# Voltage_Controlled_Amplifier_v1.net
KiCad netlist of a schematic drawn in EAGLE
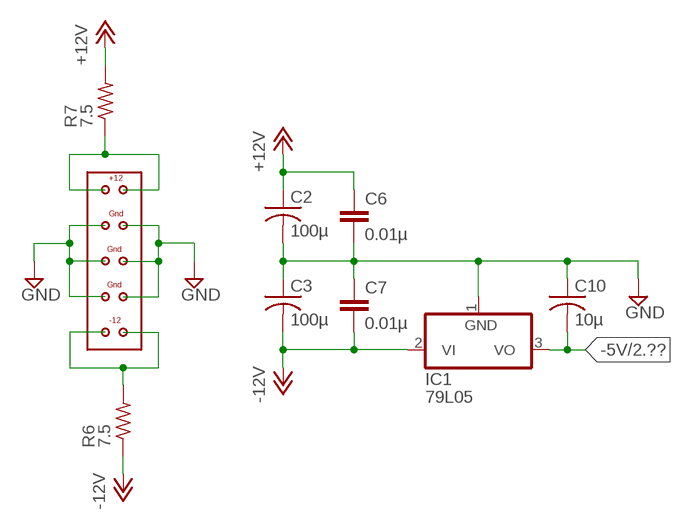
[diagram p0: schematic, sheet 1]
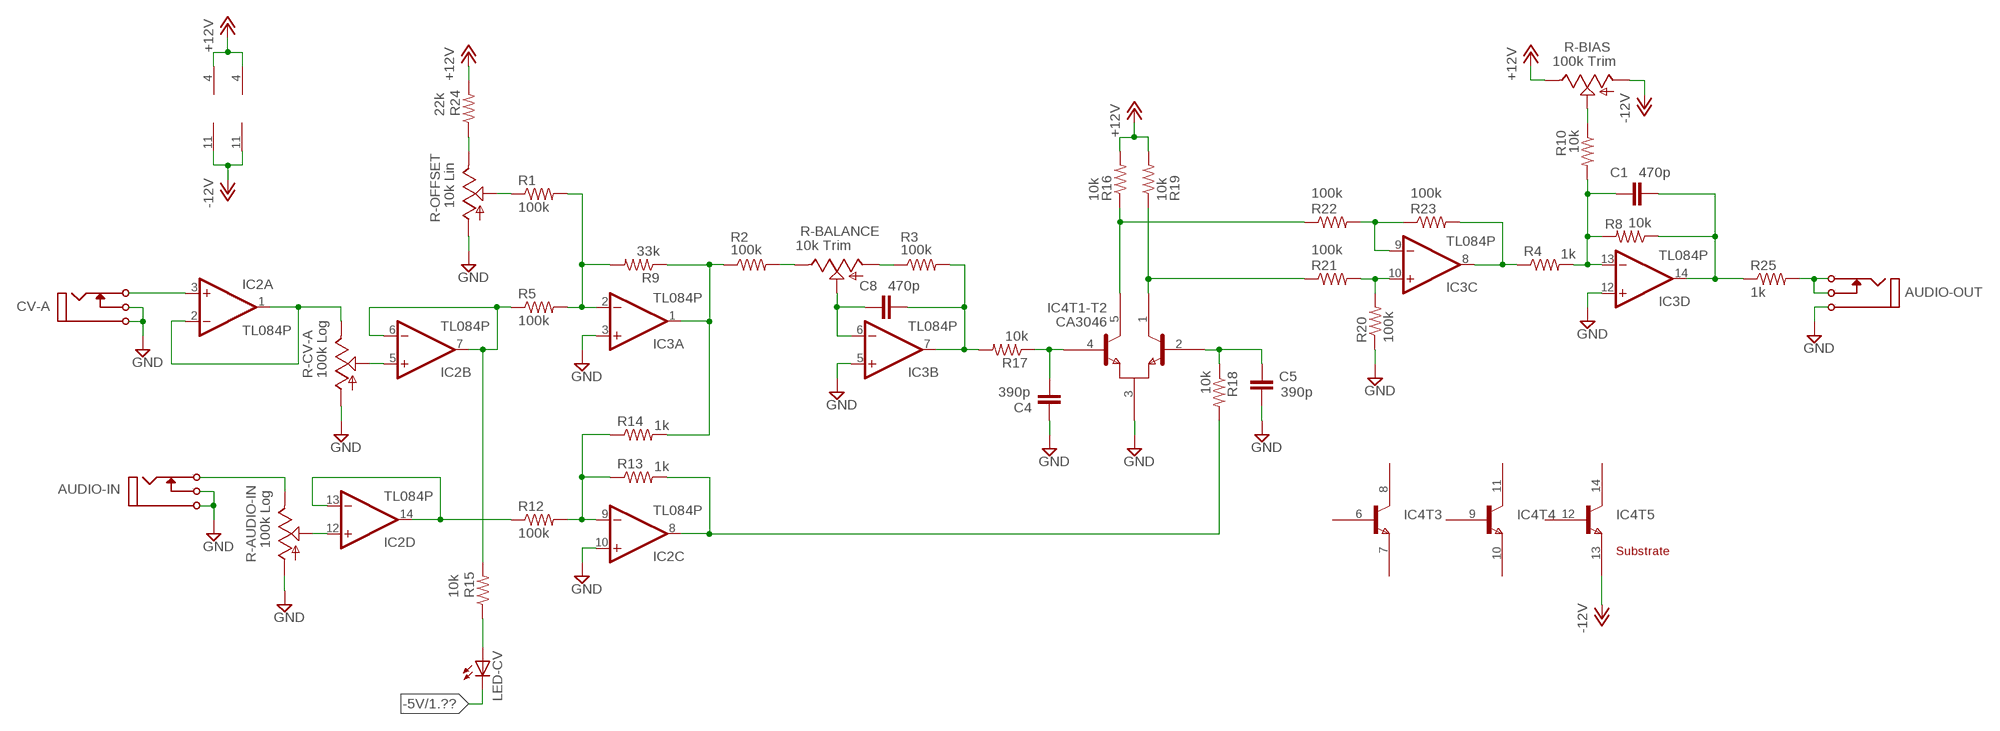
[diagram p1: schematic, sheet 2]

(export (version "E")
  (design (tool "Eeschema 10.0.6"))
  (components
    (comp (ref "AUDIO-IN")
      (value "I/O")
      (footprint "eagle-import:MONO_JACK")
      (libsource (lib "eagle-import") (part "MONO_JACK"))
    )
    (comp (ref "AUDIO-OUT")
      (value "I/O")
      (footprint "eagle-import:MONO_JACK")
      (libsource (lib "eagle-import") (part "MONO_JACK"))
    )
    (comp (ref "C1")
      (value "470p")
      (footprint "eagle-import:C2.5-2")
      (libsource (lib "eagle-import") (part "C2.5/2"))
    )
    (comp (ref "C4")
      (value "390p")
      (footprint "eagle-import:C2.5-2")
      (libsource (lib "eagle-import") (part "C2.5/2"))
    )
    (comp (ref "C5")
      (value "390p")
      (footprint "eagle-import:C2.5-2")
      (libsource (lib "eagle-import") (part "C2.5/2"))
    )
    (comp (ref "C8")
      (value "470p")
      (footprint "eagle-import:C2.5-2")
      (libsource (lib "eagle-import") (part "C2.5/2"))
    )
    (comp (ref "CV-A")
      (value "I/O")
      (footprint "eagle-import:MONO_JACK")
      (libsource (lib "eagle-import") (part "MONO_JACK"))
    )
    (comp (ref "IC2")
      (value "TL084P")
      (footprint "eagle-import:DIL14")
      (libsource (lib "eagle-import") (part "TL084P"))
    )
    (comp (ref "IC3")
      (value "TL084P")
      (footprint "eagle-import:DIL14")
      (libsource (lib "eagle-import") (part "TL084P"))
    )
    (comp (ref "IC4")
      (value "CA3046")
      (footprint "eagle-import:DIL14")
      (libsource (lib "eagle-import") (part "CA3046"))
    )
    (comp (ref "LED-CV")
      (value "TLLG4400")
      (footprint "eagle-import:LED3MM")
      (fields (field (name "MF") "VISHAY SEMICONDUCTOR"))
      (libsource (lib "eagle-import") (part "TLLG4400"))
    )
    (comp (ref "R-AUDIO-IN")
      (value "100k Log")
      (footprint "eagle-import:B64Y")
      (libsource (lib "eagle-import") (part "TRIM_US-B64Y"))
    )
    (comp (ref "R-BALANCE")
      (value "10k Trim")
      (footprint "eagle-import:B64Y")
      (libsource (lib "eagle-import") (part "TRIM_US-B64Y"))
    )
    (comp (ref "R-BIAS")
      (value "100k Trim")
      (footprint "eagle-import:B64Y")
      (libsource (lib "eagle-import") (part "TRIM_US-B64Y"))
    )
    (comp (ref "R-CV-A")
      (value "100k Log")
      (footprint "eagle-import:B64Y")
      (libsource (lib "eagle-import") (part "TRIM_US-B64Y"))
    )
    (comp (ref "R-OFFSET")
      (value "10k Lin")
      (footprint "eagle-import:B64Y")
      (libsource (lib "eagle-import") (part "TRIM_US-B64Y"))
    )
    (comp (ref "R1")
      (value "100k")
      (footprint "eagle-import:0204V")
      (libsource (lib "eagle-import") (part "R-US_0204/2V"))
    )
    (comp (ref "R2")
      (value "100k")
      (footprint "eagle-import:0204V")
      (libsource (lib "eagle-import") (part "R-US_0204/2V"))
    )
    (comp (ref "R3")
      (value "100k")
      (footprint "eagle-import:0204V")
      (libsource (lib "eagle-import") (part "R-US_0204/2V"))
    )
    (comp (ref "R4")
      (value "1k")
      (footprint "eagle-import:0204V")
      (libsource (lib "eagle-import") (part "R-US_0204/2V"))
    )
    (comp (ref "R5")
      (value "100k")
      (footprint "eagle-import:0204V")
      (libsource (lib "eagle-import") (part "R-US_0204/2V"))
    )
    (comp (ref "R8")
      (value "10k")
      (footprint "eagle-import:0204V")
      (libsource (lib "eagle-import") (part "R-US_0204/2V"))
    )
    (comp (ref "R9")
      (value "33k")
      (footprint "eagle-import:0204V")
      (libsource (lib "eagle-import") (part "R-US_0204/2V"))
    )
    (comp (ref "R10")
      (value "10k")
      (footprint "eagle-import:0204V")
      (libsource (lib "eagle-import") (part "R-US_0204/2V"))
    )
    (comp (ref "R12")
      (value "100k")
      (footprint "eagle-import:0204V")
      (libsource (lib "eagle-import") (part "R-US_0204/2V"))
    )
    (comp (ref "R13")
      (value "1k")
      (footprint "eagle-import:0204V")
      (libsource (lib "eagle-import") (part "R-US_0204/2V"))
    )
    (comp (ref "R14")
      (value "1k")
      (footprint "eagle-import:0204V")
      (libsource (lib "eagle-import") (part "R-US_0204/2V"))
    )
    (comp (ref "R15")
      (value "10k")
      (footprint "eagle-import:0204V")
      (libsource (lib "eagle-import") (part "R-US_0204/2V"))
    )
    (comp (ref "R16")
      (value "10k")
      (footprint "eagle-import:0204V")
      (libsource (lib "eagle-import") (part "R-US_0204/2V"))
    )
    (comp (ref "R17")
      (value "10k")
      (footprint "eagle-import:0204V")
      (libsource (lib "eagle-import") (part "R-US_0204/2V"))
    )
    (comp (ref "R18")
      (value "10k")
      (footprint "eagle-import:0204_7")
      (libsource (lib "eagle-import") (part "R-US_0204/7"))
    )
    (comp (ref "R19")
      (value "10k")
      (footprint "eagle-import:0204V")
      (libsource (lib "eagle-import") (part "R-US_0204/2V"))
    )
    (comp (ref "R20")
      (value "100k")
      (footprint "eagle-import:0204V")
      (libsource (lib "eagle-import") (part "R-US_0204/2V"))
    )
    (comp (ref "R21")
      (value "100k")
      (footprint "eagle-import:0204V")
      (libsource (lib "eagle-import") (part "R-US_0204/2V"))
    )
    (comp (ref "R22")
      (value "100k")
      (footprint "eagle-import:0204V")
      (libsource (lib "eagle-import") (part "R-US_0204/2V"))
    )
    (comp (ref "R23")
      (value "100k")
      (footprint "eagle-import:0204V")
      (libsource (lib "eagle-import") (part "R-US_0204/2V"))
    )
    (comp (ref "R24")
      (value "22k")
      (footprint "eagle-import:0204V")
      (libsource (lib "eagle-import") (part "R-US_0204/2V"))
    )
    (comp (ref "R25")
      (value "1k")
      (footprint "eagle-import:0204_7")
      (libsource (lib "eagle-import") (part "R-US_0204/7"))
    )
    (comp (ref "C2")
      (value "100µ")
      (footprint "eagle-import:C025-050X050")
      (libsource (lib "eagle-import") (part "C-US025-050X050"))
    )
    (comp (ref "C3")
      (value "100µ")
      (footprint "eagle-import:C025-050X050")
      (libsource (lib "eagle-import") (part "C-US025-050X050"))
    )
    (comp (ref "C6")
      (value "0.01µ")
      (footprint "eagle-import:C2.5-2")
      (libsource (lib "eagle-import") (part "C2.5/2"))
    )
    (comp (ref "C7")
      (value "0.01µ")
      (footprint "eagle-import:C2.5-2")
      (libsource (lib "eagle-import") (part "C2.5/2"))
    )
    (comp (ref "C10")
      (value "10µ")
      (footprint "eagle-import:C025-050X050")
      (libsource (lib "eagle-import") (part "C-US025-050X050"))
    )
    (comp (ref "IC1")
      (value "79L05")
      (footprint "eagle-import:TO92")
      (libsource (lib "eagle-import") (part "79ZL05"))
    )
    (comp (ref "R6")
      (value "7.5")
      (footprint "eagle-import:0204_7")
      (libsource (lib "eagle-import") (part "R-US_0204/7"))
    )
    (comp (ref "R7")
      (value "7.5")
      (footprint "eagle-import:0204_7")
      (libsource (lib "eagle-import") (part "R-US_0204/7"))
    )
    (comp (ref "U$1")
      (value "EURORACK-POWER")
      (footprint "eagle-import:EURORACK-POWER")
      (libsource (lib "eagle-import") (part "EURORACK-POWER"))
    )
  )
  (nets
    (net (code "1") (name "+12V") (class "Default")
      (node (ref "C2") (pin "1") (pinfunction "1_1") (pintype "passive"))
      (node (ref "C6") (pin "1") (pinfunction "1_1") (pintype "passive"))
      (node (ref "IC2") (pin "4") (pinfunction "V+_4") (pintype "power_in"))
      (node (ref "IC3") (pin "4") (pinfunction "V+_4") (pintype "power_in"))
      (node (ref "R-BIAS") (pin "E") (pinfunction "E_E") (pintype "passive"))
      (node (ref "R16") (pin "2") (pinfunction "2_2") (pintype "passive"))
      (node (ref "R19") (pin "2") (pinfunction "2_2") (pintype "passive"))
      (node (ref "R24") (pin "2") (pinfunction "2_2") (pintype "passive"))
      (node (ref "R7") (pin "2") (pinfunction "2_2") (pintype "passive"))
    )
    (net (code "2") (name "-5V") (class "Default")
      (node (ref "C10") (pin "2") (pinfunction "2_2") (pintype "passive"))
      (node (ref "IC1") (pin "3") (pinfunction "VO_3") (pintype "passive"))
      (node (ref "LED-CV") (pin "K") (pinfunction "C_K") (pintype "passive"))
    )
    (net (code "3") (name "-12V") (class "Default")
      (node (ref "C3") (pin "2") (pinfunction "2_2") (pintype "passive"))
      (node (ref "C7") (pin "2") (pinfunction "2_2") (pintype "passive"))
      (node (ref "IC1") (pin "2") (pinfunction "VI_2") (pintype "input"))
      (node (ref "IC2") (pin "11") (pinfunction "V-_11") (pintype "power_in"))
      (node (ref "IC3") (pin "11") (pinfunction "V-_11") (pintype "power_in"))
      (node (ref "IC4") (pin "13") (pinfunction "E_13") (pintype "passive"))
      (node (ref "R-BIAS") (pin "A") (pinfunction "A_A") (pintype "passive"))
      (node (ref "R6") (pin "1") (pinfunction "1_1") (pintype "passive"))
    )
    (net (code "4") (name "GND") (class "Default")
      (node (ref "AUDIO-IN") (pin "P$1") (pinfunction "P$1_P$1") (pintype "bidirectional"))
      (node (ref "AUDIO-IN") (pin "P$3") (pinfunction "P3_P$3") (pintype "bidirectional"))
      (node (ref "AUDIO-OUT") (pin "P$1") (pinfunction "P$1_P$1") (pintype "bidirectional"))
      (node (ref "C10") (pin "1") (pinfunction "1_1") (pintype "passive"))
      (node (ref "C2") (pin "2") (pinfunction "2_2") (pintype "passive"))
      (node (ref "C3") (pin "1") (pinfunction "1_1") (pintype "passive"))
      (node (ref "C4") (pin "1") (pinfunction "1_1") (pintype "passive"))
      (node (ref "C5") (pin "2") (pinfunction "2_2") (pintype "passive"))
      (node (ref "C6") (pin "2") (pinfunction "2_2") (pintype "passive"))
      (node (ref "C7") (pin "1") (pinfunction "1_1") (pintype "passive"))
      (node (ref "CV-A") (pin "P$1") (pinfunction "P$1_P$1") (pintype "bidirectional"))
      (node (ref "CV-A") (pin "P$3") (pinfunction "P3_P$3") (pintype "bidirectional"))
      (node (ref "IC1") (pin "1") (pinfunction "GND_1") (pintype "passive"))
      (node (ref "IC2") (pin "10") (pinfunction "+IN_10") (pintype "input"))
      (node (ref "IC3") (pin "12") (pinfunction "+IN_12") (pintype "input"))
      (node (ref "IC3") (pin "3") (pinfunction "+IN_3") (pintype "input"))
      (node (ref "IC3") (pin "5") (pinfunction "+IN_5") (pintype "input"))
      (node (ref "IC4") (pin "3") (pinfunction "E_3") (pintype "passive"))
      (node (ref "R-AUDIO-IN") (pin "A") (pinfunction "A_A") (pintype "passive"))
      (node (ref "R-CV-A") (pin "A") (pinfunction "A_A") (pintype "passive"))
      (node (ref "R-OFFSET") (pin "A") (pinfunction "A_A") (pintype "passive"))
      (node (ref "R20") (pin "1") (pinfunction "1_1") (pintype "passive"))
      (node (ref "U$1") (pin "P$3") (pinfunction "P$3_P$3") (pintype "bidirectional"))
      (node (ref "U$1") (pin "P$4") (pinfunction "P$4_P$4") (pintype "bidirectional"))
      (node (ref "U$1") (pin "P$5") (pinfunction "P$5_P$5") (pintype "bidirectional"))
      (node (ref "U$1") (pin "P$6") (pinfunction "P$6_P$6") (pintype "bidirectional"))
      (node (ref "U$1") (pin "P$7") (pinfunction "P$7_P$7") (pintype "bidirectional"))
      (node (ref "U$1") (pin "P$8") (pinfunction "P$8_P$8") (pintype "bidirectional"))
    )
    (net (code "5") (name "Net-(AUDIO-IN-P2)") (class "Default")
      (node (ref "AUDIO-IN") (pin "P$2") (pinfunction "P2_P$2") (pintype "bidirectional"))
      (node (ref "R-AUDIO-IN") (pin "E") (pinfunction "E_E") (pintype "passive"))
    )
    (net (code "6") (name "Net-(AUDIO-OUT-P2)") (class "Default")
      (node (ref "AUDIO-OUT") (pin "P$2") (pinfunction "P2_P$2") (pintype "bidirectional"))
      (node (ref "AUDIO-OUT") (pin "P$3") (pinfunction "P3_P$3") (pintype "bidirectional"))
      (node (ref "R25") (pin "2") (pinfunction "2_2") (pintype "passive"))
    )
    (net (code "7") (name "Net-(CV-A-P2)") (class "Default")
      (node (ref "CV-A") (pin "P$2") (pinfunction "P2_P$2") (pintype "bidirectional"))
      (node (ref "IC2") (pin "3") (pinfunction "+IN_3") (pintype "input"))
    )
    (net (code "8") (name "Net-(IC2A--IN)") (class "Default")
      (node (ref "IC2") (pin "1") (pinfunction "OUT_1") (pintype "output"))
      (node (ref "IC2") (pin "2") (pinfunction "-IN_2") (pintype "input"))
      (node (ref "R-CV-A") (pin "E") (pinfunction "E_E") (pintype "passive"))
    )
    (net (code "9") (name "Net-(IC2B-+IN)") (class "Default")
      (node (ref "IC2") (pin "5") (pinfunction "+IN_5") (pintype "input"))
      (node (ref "R-CV-A") (pin "S") (pinfunction "S_S") (pintype "passive"))
    )
    (net (code "10") (name "Net-(IC2B--IN)") (class "Default")
      (node (ref "IC2") (pin "6") (pinfunction "-IN_6") (pintype "input"))
      (node (ref "IC2") (pin "7") (pinfunction "OUT_7") (pintype "output"))
      (node (ref "R15") (pin "2") (pinfunction "2_2") (pintype "passive"))
      (node (ref "R5") (pin "1") (pinfunction "1_1") (pintype "passive"))
    )
    (net (code "11") (name "Net-(IC2C--IN)") (class "Default")
      (node (ref "IC2") (pin "9") (pinfunction "-IN_9") (pintype "input"))
      (node (ref "R12") (pin "2") (pinfunction "2_2") (pintype "passive"))
      (node (ref "R13") (pin "1") (pinfunction "1_1") (pintype "passive"))
      (node (ref "R14") (pin "1") (pinfunction "1_1") (pintype "passive"))
    )
    (net (code "12") (name "Net-(IC2C-OUT)") (class "Default")
      (node (ref "IC2") (pin "8") (pinfunction "OUT_8") (pintype "output"))
      (node (ref "R13") (pin "2") (pinfunction "2_2") (pintype "passive"))
      (node (ref "R18") (pin "2") (pinfunction "2_2") (pintype "passive"))
    )
    (net (code "13") (name "Net-(IC2D-+IN)") (class "Default")
      (node (ref "IC2") (pin "12") (pinfunction "+IN_12") (pintype "input"))
      (node (ref "R-AUDIO-IN") (pin "S") (pinfunction "S_S") (pintype "passive"))
    )
    (net (code "14") (name "Net-(IC2D--IN)") (class "Default")
      (node (ref "IC2") (pin "13") (pinfunction "-IN_13") (pintype "input"))
      (node (ref "IC2") (pin "14") (pinfunction "OUT_14") (pintype "output"))
      (node (ref "R12") (pin "1") (pinfunction "1_1") (pintype "passive"))
    )
    (net (code "15") (name "Net-(IC3A--IN)") (class "Default")
      (node (ref "IC3") (pin "2") (pinfunction "-IN_2") (pintype "input"))
      (node (ref "R1") (pin "2") (pinfunction "2_2") (pintype "passive"))
      (node (ref "R5") (pin "2") (pinfunction "2_2") (pintype "passive"))
      (node (ref "R9") (pin "2") (pinfunction "2_2") (pintype "passive"))
    )
    (net (code "16") (name "Net-(IC3A-OUT)") (class "Default")
      (node (ref "IC3") (pin "1") (pinfunction "OUT_1") (pintype "output"))
      (node (ref "R14") (pin "2") (pinfunction "2_2") (pintype "passive"))
      (node (ref "R2") (pin "1") (pinfunction "1_1") (pintype "passive"))
      (node (ref "R9") (pin "1") (pinfunction "1_1") (pintype "passive"))
    )
    (net (code "17") (name "Net-(IC3B--IN)") (class "Default")
      (node (ref "C8") (pin "1") (pinfunction "1_1") (pintype "passive"))
      (node (ref "IC3") (pin "6") (pinfunction "-IN_6") (pintype "input"))
      (node (ref "R-BALANCE") (pin "S") (pinfunction "S_S") (pintype "passive"))
    )
    (net (code "18") (name "Net-(IC3B-OUT)") (class "Default")
      (node (ref "C8") (pin "2") (pinfunction "2_2") (pintype "passive"))
      (node (ref "IC3") (pin "7") (pinfunction "OUT_7") (pintype "output"))
      (node (ref "R17") (pin "2") (pinfunction "2_2") (pintype "passive"))
      (node (ref "R3") (pin "2") (pinfunction "2_2") (pintype "passive"))
    )
    (net (code "19") (name "Net-(IC3C-+IN)") (class "Default")
      (node (ref "IC3") (pin "10") (pinfunction "+IN_10") (pintype "input"))
      (node (ref "R20") (pin "2") (pinfunction "2_2") (pintype "passive"))
      (node (ref "R21") (pin "2") (pinfunction "2_2") (pintype "passive"))
    )
    (net (code "20") (name "Net-(IC3C--IN)") (class "Default")
      (node (ref "IC3") (pin "9") (pinfunction "-IN_9") (pintype "input"))
      (node (ref "R22") (pin "2") (pinfunction "2_2") (pintype "passive"))
      (node (ref "R23") (pin "1") (pinfunction "1_1") (pintype "passive"))
    )
    (net (code "21") (name "Net-(IC3C-OUT)") (class "Default")
      (node (ref "IC3") (pin "8") (pinfunction "OUT_8") (pintype "output"))
      (node (ref "R23") (pin "2") (pinfunction "2_2") (pintype "passive"))
      (node (ref "R4") (pin "1") (pinfunction "1_1") (pintype "passive"))
    )
    (net (code "22") (name "Net-(IC3D--IN)") (class "Default")
      (node (ref "C1") (pin "1") (pinfunction "1_1") (pintype "passive"))
      (node (ref "IC3") (pin "13") (pinfunction "-IN_13") (pintype "input"))
      (node (ref "R10") (pin "2") (pinfunction "2_2") (pintype "passive"))
      (node (ref "R4") (pin "2") (pinfunction "2_2") (pintype "passive"))
      (node (ref "R8") (pin "2") (pinfunction "2_2") (pintype "passive"))
    )
    (net (code "23") (name "Net-(IC3D-OUT)") (class "Default")
      (node (ref "C1") (pin "2") (pinfunction "2_2") (pintype "passive"))
      (node (ref "IC3") (pin "14") (pinfunction "OUT_14") (pintype "output"))
      (node (ref "R25") (pin "1") (pinfunction "1_1") (pintype "passive"))
      (node (ref "R8") (pin "1") (pinfunction "1_1") (pintype "passive"))
    )
    (net (code "24") (name "Net-(IC4A-B1)") (class "Default")
      (node (ref "C5") (pin "1") (pinfunction "1_1") (pintype "passive"))
      (node (ref "IC4") (pin "2") (pinfunction "B1_2") (pintype "passive"))
      (node (ref "R18") (pin "1") (pinfunction "1_1") (pintype "passive"))
    )
    (net (code "25") (name "Net-(IC4A-B2)") (class "Default")
      (node (ref "C4") (pin "2") (pinfunction "2_2") (pintype "passive"))
      (node (ref "IC4") (pin "4") (pinfunction "B2_4") (pintype "passive"))
      (node (ref "R17") (pin "1") (pinfunction "1_1") (pintype "passive"))
    )
    (net (code "26") (name "Net-(IC4A-C1)") (class "Default")
      (node (ref "IC4") (pin "1") (pinfunction "C1_1") (pintype "passive"))
      (node (ref "R19") (pin "1") (pinfunction "1_1") (pintype "passive"))
      (node (ref "R21") (pin "1") (pinfunction "1_1") (pintype "passive"))
    )
    (net (code "27") (name "Net-(IC4A-C2)") (class "Default")
      (node (ref "IC4") (pin "5") (pinfunction "C2_5") (pintype "passive"))
      (node (ref "R16") (pin "1") (pinfunction "1_1") (pintype "passive"))
      (node (ref "R22") (pin "1") (pinfunction "1_1") (pintype "passive"))
    )
    (net (code "28") (name "Net-(LED-CV-PadA)") (class "Default")
      (node (ref "LED-CV") (pin "A") (pinfunction "A_A") (pintype "passive"))
      (node (ref "R15") (pin "1") (pinfunction "1_1") (pintype "passive"))
    )
    (net (code "29") (name "Net-(R-BALANCE-PadA)") (class "Default")
      (node (ref "R-BALANCE") (pin "A") (pinfunction "A_A") (pintype "passive"))
      (node (ref "R3") (pin "1") (pinfunction "1_1") (pintype "passive"))
    )
    (net (code "30") (name "Net-(R-BALANCE-PadE)") (class "Default")
      (node (ref "R-BALANCE") (pin "E") (pinfunction "E_E") (pintype "passive"))
      (node (ref "R2") (pin "2") (pinfunction "2_2") (pintype "passive"))
    )
    (net (code "31") (name "Net-(R-BIAS-PadS)") (class "Default")
      (node (ref "R-BIAS") (pin "S") (pinfunction "S_S") (pintype "passive"))
      (node (ref "R10") (pin "1") (pinfunction "1_1") (pintype "passive"))
    )
    (net (code "32") (name "Net-(R-OFFSET-PadE)") (class "Default")
      (node (ref "R-OFFSET") (pin "E") (pinfunction "E_E") (pintype "passive"))
      (node (ref "R24") (pin "1") (pinfunction "1_1") (pintype "passive"))
    )
    (net (code "33") (name "Net-(R-OFFSET-PadS)") (class "Default")
      (node (ref "R-OFFSET") (pin "S") (pinfunction "S_S") (pintype "passive"))
      (node (ref "R1") (pin "1") (pinfunction "1_1") (pintype "passive"))
    )
    (net (code "34") (name "Net-(R6-Pad2)") (class "Default")
      (node (ref "R6") (pin "2") (pinfunction "2_2") (pintype "passive"))
      (node (ref "U$1") (pin "P$10") (pinfunction "P$10_P$10") (pintype "bidirectional"))
      (node (ref "U$1") (pin "P$9") (pinfunction "P$9_P$9") (pintype "bidirectional"))
    )
    (net (code "35") (name "Net-(R7-Pad1)") (class "Default")
      (node (ref "R7") (pin "1") (pinfunction "1_1") (pintype "passive"))
      (node (ref "U$1") (pin "P$1") (pinfunction "P$1_P$1") (pintype "bidirectional"))
      (node (ref "U$1") (pin "P$2") (pinfunction "P$2_P$2") (pintype "bidirectional"))
    )
    (net (code "36") (name "unconnected-(IC4B-B-Pad6)") (class "Default")
      (node (ref "IC4") (pin "6") (pinfunction "B_6") (pintype "passive"))
    )
    (net (code "37") (name "unconnected-(IC4B-C-Pad8)") (class "Default")
      (node (ref "IC4") (pin "8") (pinfunction "C_8") (pintype "passive"))
    )
    (net (code "38") (name "unconnected-(IC4B-E-Pad7)") (class "Default")
      (node (ref "IC4") (pin "7") (pinfunction "E_7") (pintype "passive"))
    )
    (net (code "39") (name "unconnected-(IC4C-B-Pad9)") (class "Default")
      (node (ref "IC4") (pin "9") (pinfunction "B_9") (pintype "passive"))
    )
    (net (code "40") (name "unconnected-(IC4C-C-Pad11)") (class "Default")
      (node (ref "IC4") (pin "11") (pinfunction "C_11") (pintype "passive"))
    )
    (net (code "41") (name "unconnected-(IC4C-E-Pad10)") (class "Default")
      (node (ref "IC4") (pin "10") (pinfunction "E_10") (pintype "passive"))
    )
    (net (code "42") (name "unconnected-(IC4D-B-Pad12)") (class "Default")
      (node (ref "IC4") (pin "12") (pinfunction "B_12") (pintype "passive"))
    )
    (net (code "43") (name "unconnected-(IC4D-C-Pad14)") (class "Default")
      (node (ref "IC4") (pin "14") (pinfunction "C_14") (pintype "passive"))
    )
  )
)
